# MIXER.net
KiCad netlist of a schematic drawn in Altium Designer
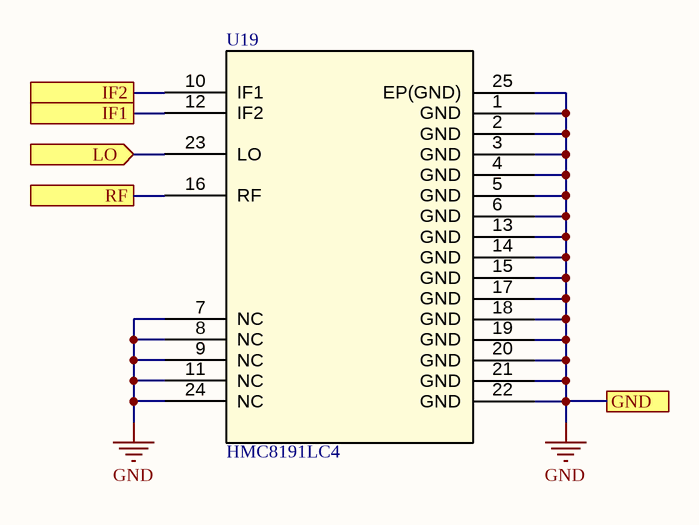
[diagram p0: MIXER.SchDoc]

(export (version "E")
  (design (tool "Eeschema 10.0.6"))
  (components
    (comp (ref "U19")
      (value "HMC8191LC4")
      (footprint "HMC8191_E-24-1")
      (description "6 GHz to 26.5 GHz,\r\nWideband I/Q Mixer")
      (fields (field (name "COPYRIGHT") "Copyright (C) 2018 Accelerated Designs. All rights reserved"))
      (libsource (lib "FullyDigital") (part "HMC8191LC4"))
    )
  )
  (nets
    (net (code "1") (name "/IF1") (class "Default")
      (node (ref "U19") (pin "12") (pinfunction "IF2_12") (pintype "passive"))
    )
    (net (code "2") (name "/IF2") (class "Default")
      (node (ref "U19") (pin "10") (pinfunction "IF1_10") (pintype "passive"))
    )
    (net (code "3") (name "/LO") (class "Default")
      (node (ref "U19") (pin "23") (pinfunction "LO_23") (pintype "passive"))
    )
    (net (code "4") (name "/RF") (class "Default")
      (node (ref "U19") (pin "16") (pinfunction "RF_16") (pintype "passive"))
    )
    (net (code "5") (name "GND") (class "Default")
      (node (ref "U19") (pin "1") (pinfunction "GND_1") (pintype "passive"))
      (node (ref "U19") (pin "11") (pinfunction "NC_11") (pintype "passive"))
      (node (ref "U19") (pin "13") (pinfunction "GND_13") (pintype "passive"))
      (node (ref "U19") (pin "14") (pinfunction "GND_14") (pintype "passive"))
      (node (ref "U19") (pin "15") (pinfunction "GND_15") (pintype "passive"))
      (node (ref "U19") (pin "17") (pinfunction "GND_17") (pintype "passive"))
      (node (ref "U19") (pin "18") (pinfunction "GND_18") (pintype "passive"))
      (node (ref "U19") (pin "19") (pinfunction "GND_19") (pintype "passive"))
      (node (ref "U19") (pin "2") (pinfunction "GND_2") (pintype "passive"))
      (node (ref "U19") (pin "20") (pinfunction "GND_20") (pintype "passive"))
      (node (ref "U19") (pin "21") (pinfunction "GND_21") (pintype "passive"))
      (node (ref "U19") (pin "22") (pinfunction "GND_22") (pintype "passive"))
      (node (ref "U19") (pin "24") (pinfunction "NC_24") (pintype "passive"))
      (node (ref "U19") (pin "25") (pinfunction "EP(GND)_25") (pintype "passive"))
      (node (ref "U19") (pin "3") (pinfunction "GND_3") (pintype "passive"))
      (node (ref "U19") (pin "4") (pinfunction "GND_4") (pintype "passive"))
      (node (ref "U19") (pin "5") (pinfunction "GND_5") (pintype "passive"))
      (node (ref "U19") (pin "6") (pinfunction "GND_6") (pintype "passive"))
      (node (ref "U19") (pin "7") (pinfunction "NC_7") (pintype "passive"))
      (node (ref "U19") (pin "8") (pinfunction "NC_8") (pintype "passive"))
      (node (ref "U19") (pin "9") (pinfunction "NC_9") (pintype "passive"))
    )
  )
)
